# 05_Ethernet.net
KiCad netlist of a schematic drawn in Altium Designer
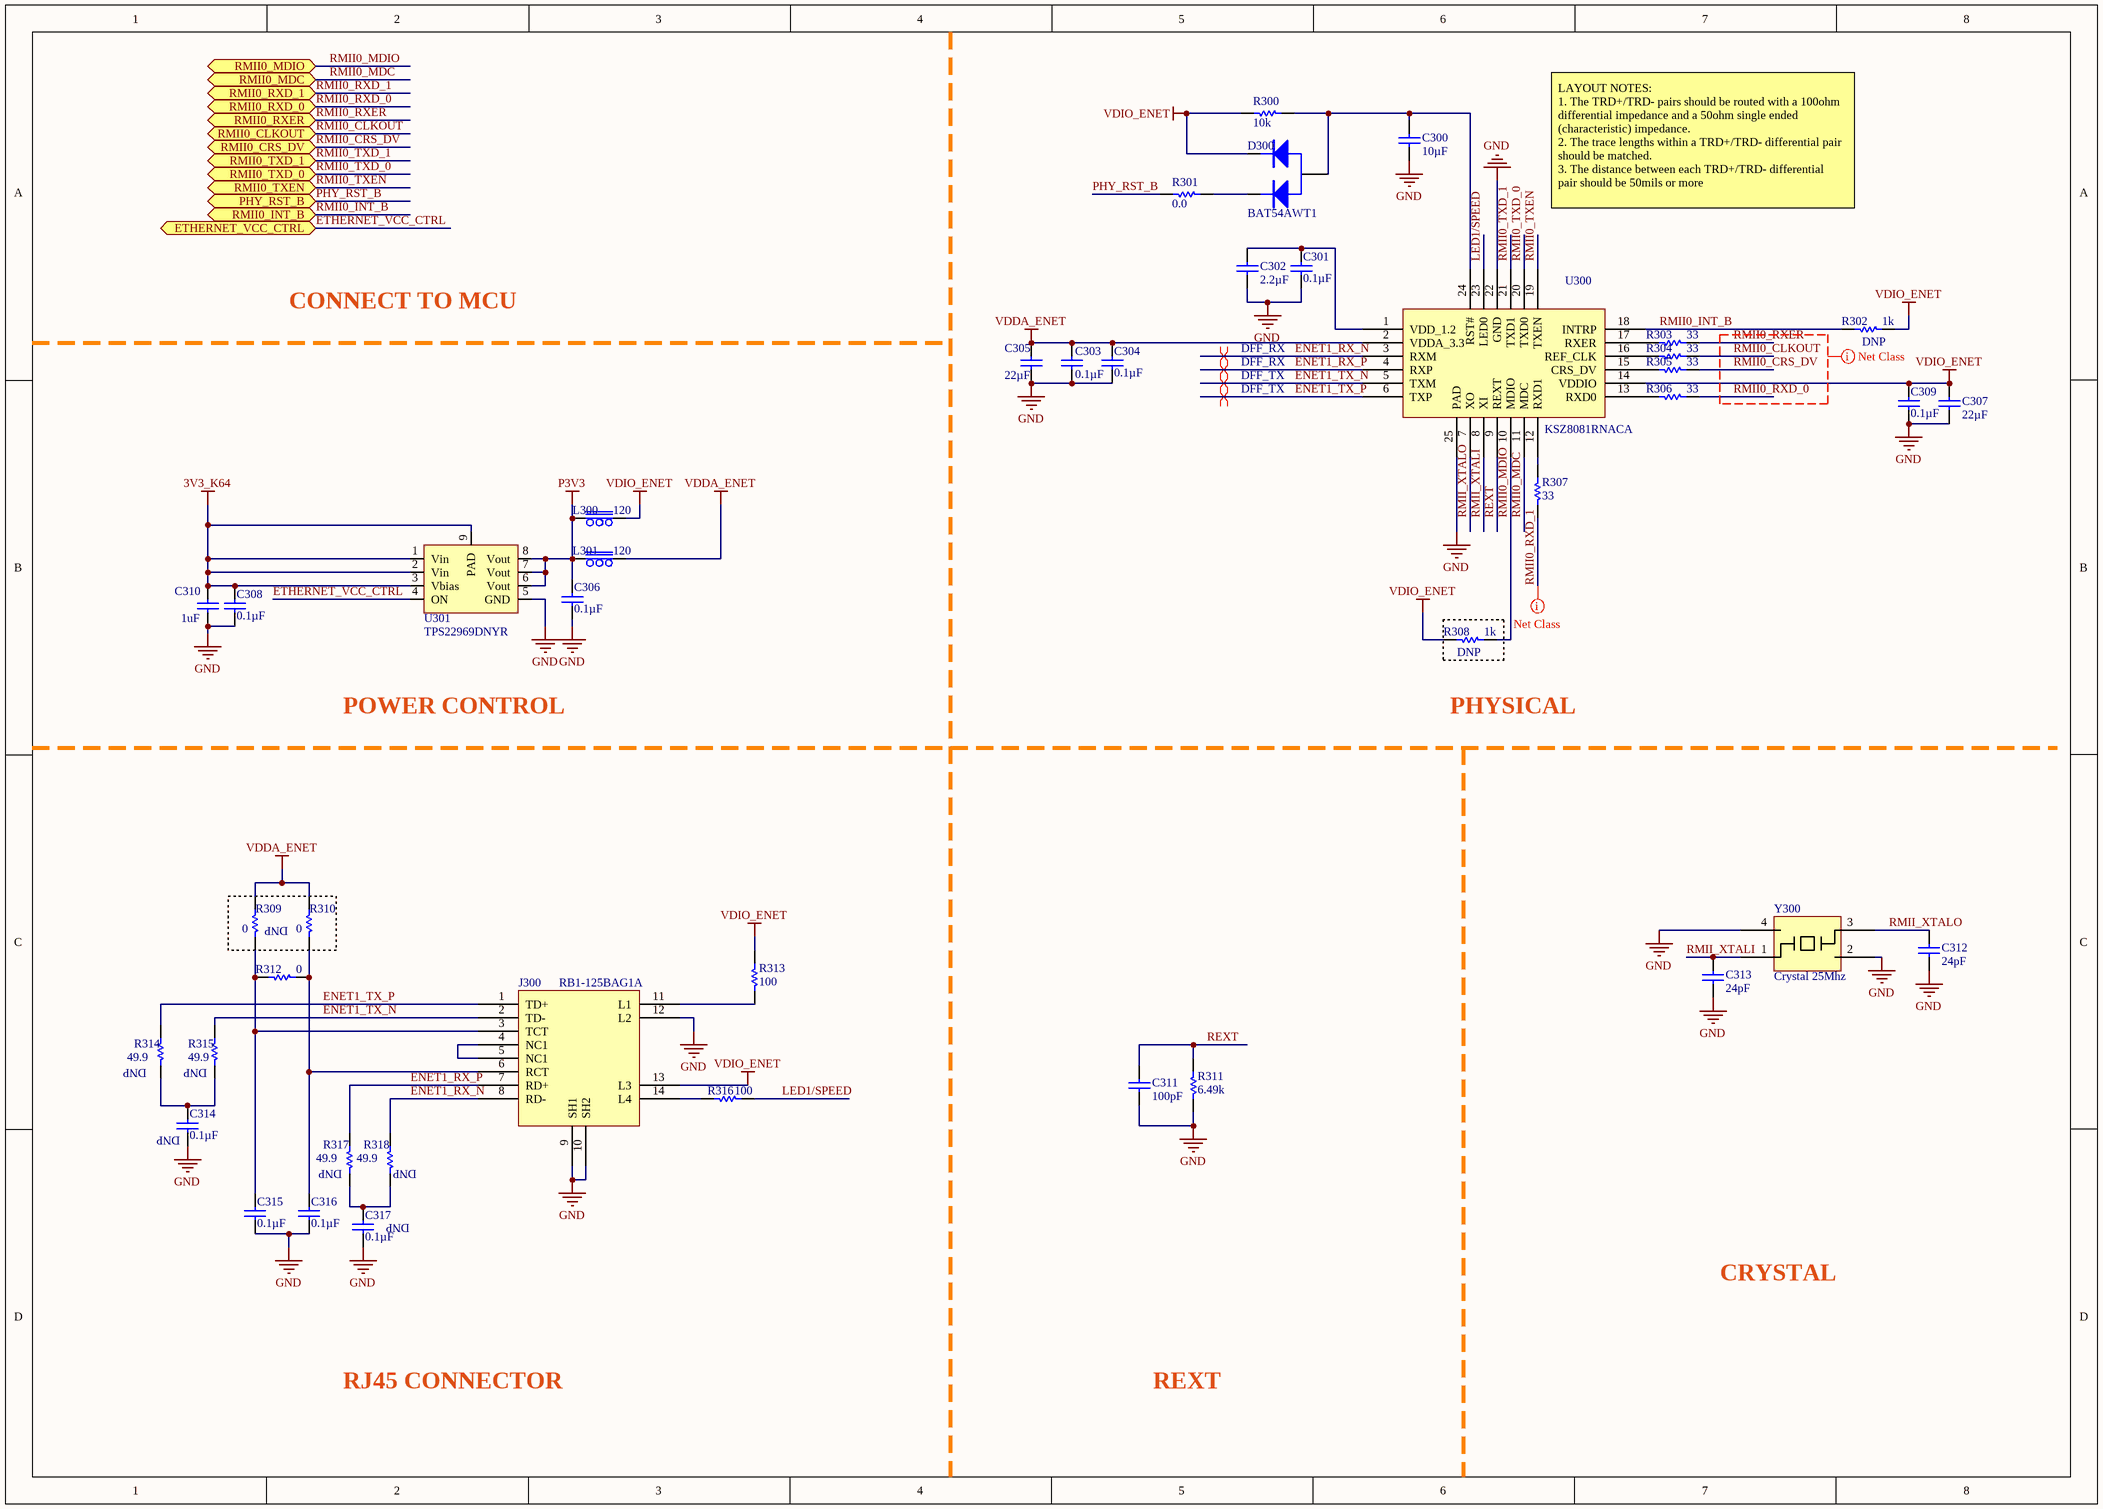
[diagram p0: [05] Ethernet.SchDoc]

(export (version "E")
  (design (tool "Eeschema 10.0.6"))
  (components
    (comp (ref "C300")
      (value "10µF")
      (footprint "0603C")
      (description "CAP CER 10UF 16V X6S 0603")
      (fields
        (field (name "MANUFACTURER") "Taiyo Yuden")
        (field (name "MANUFACTURER PART NUMBER") "EMK107BC6106MA-T")
      )
      (libsource (lib "BinhLib") (part "cap SMD"))
    )
    (comp (ref "C301")
      (value "0.1µF")
      (footprint "0402C")
      (description "CAP CER 0.1UF 10V X7R 0402")
      (fields
        (field (name "MANUFACTURER") "Taiyo Yuden")
        (field (name "MANUFACTURER PART NUMBER") "LMK105B7104KVHF")
      )
      (libsource (lib "BinhLib") (part "CAP0.1u0402"))
    )
    (comp (ref "C302")
      (value "2.2µF")
      (footprint "0402C")
      (description "CAP CER 2.2UF 16V X5R 0402")
      (fields
        (field (name "MANUFACTURER") "Taiyo Yuden")
        (field (name "MANUFACTURER PART NUMBER") "EMK105ABJ225MV-F")
      )
      (libsource (lib "BinhLib") (part "cap2.2u0402"))
    )
    (comp (ref "C303")
      (value "0.1µF")
      (footprint "0402C")
      (description "CAP CER 0.1UF 10V X7R 0402")
      (fields
        (field (name "MANUFACTURER") "Taiyo Yuden")
        (field (name "MANUFACTURER PART NUMBER") "LMK105B7104KVHF")
      )
      (libsource (lib "BinhLib") (part "CAP0.1u0402"))
    )
    (comp (ref "C304")
      (value "0.1µF")
      (footprint "0402C")
      (description "CAP CER 0.1UF 10V X7R 0402")
      (fields
        (field (name "MANUFACTURER") "Taiyo Yuden")
        (field (name "MANUFACTURER PART NUMBER") "LMK105B7104KVHF")
      )
      (libsource (lib "BinhLib") (part "CAP0.1u0402"))
    )
    (comp (ref "C305")
      (value "22µF")
      (footprint "0603C")
      (description "CAP CER 22UF 10V X5R 0603")
      (fields
        (field (name "MANUFACTURER") "Taiyo Yuden")
        (field (name "MANUFACTURER PART NUMBER") "LMK107BBJ226MA-T")
      )
      (libsource (lib "BinhLib") (part "cap SMD"))
    )
    (comp (ref "C306")
      (value "0.1µF")
      (footprint "0402C")
      (description "CAP CER 0.1UF 10V X7R 0402")
      (fields
        (field (name "MANUFACTURER") "Taiyo Yuden")
        (field (name "MANUFACTURER PART NUMBER") "LMK105B7104KVHF")
      )
      (libsource (lib "BinhLib") (part "CAP0.1u0402"))
    )
    (comp (ref "C307")
      (value "22µF")
      (footprint "0603C")
      (description "CAP CER 22UF 10V X5R 0603")
      (fields
        (field (name "MANUFACTURER") "Taiyo Yuden")
        (field (name "MANUFACTURER PART NUMBER") "LMK107BBJ226MA-T")
      )
      (libsource (lib "BinhLib") (part "cap SMD"))
    )
    (comp (ref "C308")
      (value "0.1µF")
      (footprint "0402C")
      (description "CAP CER 0.1UF 10V X7R 0402")
      (fields
        (field (name "MANUFACTURER") "Taiyo Yuden")
        (field (name "MANUFACTURER PART NUMBER") "LMK105B7104KVHF")
      )
      (libsource (lib "BinhLib") (part "CAP0.1u0402"))
    )
    (comp (ref "C309")
      (value "0.1µF")
      (footprint "0402C")
      (description "CAP CER 0.1UF 10V X7R 0402")
      (fields
        (field (name "MANUFACTURER") "Taiyo Yuden")
        (field (name "MANUFACTURER PART NUMBER") "LMK105B7104KVHF")
      )
      (libsource (lib "BinhLib") (part "CAP0.1u0402"))
    )
    (comp (ref "C310")
      (value "1uF")
      (footprint "0402C")
      (description "CAP CER 1UF 10V X6S 0402")
      (fields
        (field (name "MANUFACTURER") "Taiyo Yuden")
        (field (name "MANUFACTURER PART NUMBER") "LMK105C6105KV-F")
      )
      (libsource (lib "BinhLib") (part "cap SMD"))
    )
    (comp (ref "C311")
      (value "100pF")
      (footprint "0603C")
      (description "CAP CER 100PF 250V NP0 0603")
      (fields
        (field (name "MANUFACTURER") "Taiyo Yuden")
        (field (name "MANUFACTURER PART NUMBER") "QVS107CG101JCHT")
      )
      (libsource (lib "BinhLib") (part "cap SMD"))
    )
    (comp (ref "C312")
      (value "24pF")
      (footprint "0402C")
      (description "CAP CER 24PF 50V NP0 0402")
      (fields
        (field (name "MANUFACTURER") "Taiyo Yuden")
        (field (name "MANUFACTURER PART NUMBER") "UMK105CG240JV-F")
      )
      (libsource (lib "BinhLib") (part "cap SMD"))
    )
    (comp (ref "C313")
      (value "24pF")
      (footprint "0402C")
      (description "CAP CER 24PF 50V NP0 0402")
      (fields
        (field (name "MANUFACTURER") "Taiyo Yuden")
        (field (name "MANUFACTURER PART NUMBER") "UMK105CG240JV-F")
      )
      (libsource (lib "BinhLib") (part "cap SMD"))
    )
    (comp (ref "C314")
      (value "0.1µF")
      (footprint "0402C")
      (description "CAP CER 0.1UF 10V X7R 0402")
      (fields
        (field (name "MANUFACTURER") "Taiyo Yuden")
        (field (name "MANUFACTURER PART NUMBER") "LMK105B7104KVHF")
      )
      (libsource (lib "BinhLib") (part "CAP0.1u0402"))
    )
    (comp (ref "C315")
      (value "0.1µF")
      (footprint "0402C")
      (description "CAP CER 0.1UF 10V X7R 0402")
      (fields
        (field (name "MANUFACTURER") "Taiyo Yuden")
        (field (name "MANUFACTURER PART NUMBER") "LMK105B7104KVHF")
      )
      (libsource (lib "BinhLib") (part "CAP0.1u0402"))
    )
    (comp (ref "C316")
      (value "0.1µF")
      (footprint "0402C")
      (description "CAP CER 0.1UF 10V X7R 0402")
      (fields
        (field (name "MANUFACTURER") "Taiyo Yuden")
        (field (name "MANUFACTURER PART NUMBER") "LMK105B7104KVHF")
      )
      (libsource (lib "BinhLib") (part "CAP0.1u0402"))
    )
    (comp (ref "C317")
      (value "0.1µF")
      (footprint "0402C")
      (description "CAP CER 0.1UF 10V X7R 0402")
      (fields
        (field (name "MANUFACTURER") "Taiyo Yuden")
        (field (name "MANUFACTURER PART NUMBER") "LMK105B7104KVHF")
      )
      (libsource (lib "BinhLib") (part "CAP0.1u0402"))
    )
    (comp (ref "D300")
      (value "BAT54AWT1")
      (footprint "SOT323")
      (description "DIODE ARRAY SCHOTTKY 30V SOT323")
      (fields
        (field (name "MANUFACTURER") "ON Semiconductor")
        (field (name "MANUFACTURER PART NUMBER") "BAT54AWT1G")
      )
      (libsource (lib "BinhLib") (part "diodes barrier"))
    )
    (comp (ref "J300")
      (value "RB1-125BAG1A")
      (footprint "RJ45 Tranfomer")
      (description "CONN MAGJACK 1PORT 100 BASE-T")
      (fields (field (name "MANUFACTURER") "WIZnet"))
      (libsource (lib "BinhLib") (part "RJ45"))
    )
    (comp (ref "L300")
      (value "120")
      (footprint "0805F")
      (fields
        (field (name "MANUFACTURER") "MURATA")
        (field (name "MANUFACTURER PART NUMBER") "BLM18PG121SN1D")
      )
      (libsource (lib "BinhLib") (part "Ferrite Bead"))
    )
    (comp (ref "L301")
      (value "120")
      (footprint "0805F")
      (fields
        (field (name "MANUFACTURER") "MURATA")
        (field (name "MANUFACTURER PART NUMBER") "BLM18PG121SN1D")
      )
      (libsource (lib "BinhLib") (part "Ferrite Bead"))
    )
    (comp (ref "R300")
      (value "10k")
      (footprint "0603R")
      (description "RES SMD 10K OHM 1% 1/10W 0603")
      (fields
        (field (name "MANUFACTURER") "Panasonic Electronic Components")
        (field (name "MANUFACTURER PART NUMBER") "ERJ-3EKF1002V")
      )
      (libsource (lib "BinhLib") (part "RES10k0603"))
    )
    (comp (ref "R301")
      (value "0.0")
      (footprint "0603R")
      (description "RES SMD 0.0OHM JUMPER 1/10W 0603")
      (fields
        (field (name "MANUFACTURER") "Panasonic Electronic Components")
        (field (name "MANUFACTURER PART NUMBER") "ERJ-3GEY0R00V")
      )
      (libsource (lib "BinhLib") (part "RES00603"))
    )
    (comp (ref "R302")
      (value "1k")
      (footprint "0402R")
      (description "RES SMD 1K OHM 1% 1/10W 0402")
      (fields
        (field (name "MANUFACTURER") "Panasonic Electronic Components")
        (field (name "MANUFACTURER PART NUMBER") "ERJ-2RKF1001X")
      )
      (libsource (lib "BinhLib") (part "RES1k0402"))
    )
    (comp (ref "R303")
      (value "33")
      (footprint "0402R")
      (description "RES SMD 33 OHM 1% 1/10W 0402")
      (fields
        (field (name "MANUFACTURER") "Panasonic Electronic Components")
        (field (name "MANUFACTURER PART NUMBER") "ERJ-2RKF33R0X")
      )
      (libsource (lib "BinhLib") (part "RES330402"))
    )
    (comp (ref "R304")
      (value "33")
      (footprint "0402R")
      (description "RES SMD 33 OHM 1% 1/10W 0402")
      (fields
        (field (name "MANUFACTURER") "Panasonic Electronic Components")
        (field (name "MANUFACTURER PART NUMBER") "ERJ-2RKF33R0X")
      )
      (libsource (lib "BinhLib") (part "RES330402"))
    )
    (comp (ref "R305")
      (value "33")
      (footprint "0402R")
      (description "RES SMD 33 OHM 1% 1/10W 0402")
      (fields
        (field (name "MANUFACTURER") "Panasonic Electronic Components")
        (field (name "MANUFACTURER PART NUMBER") "ERJ-2RKF33R0X")
      )
      (libsource (lib "BinhLib") (part "RES330402"))
    )
    (comp (ref "R306")
      (value "33")
      (footprint "0402R")
      (description "RES SMD 33 OHM 1% 1/10W 0402")
      (fields
        (field (name "MANUFACTURER") "Panasonic Electronic Components")
        (field (name "MANUFACTURER PART NUMBER") "ERJ-2RKF33R0X")
      )
      (libsource (lib "BinhLib") (part "RES330402"))
    )
    (comp (ref "R307")
      (value "33")
      (footprint "0402R")
      (description "RES SMD 33 OHM 1% 1/10W 0402")
      (fields
        (field (name "MANUFACTURER") "Panasonic Electronic Components")
        (field (name "MANUFACTURER PART NUMBER") "ERJ-2RKF33R0X")
      )
      (libsource (lib "BinhLib") (part "RES330402"))
    )
    (comp (ref "R308")
      (value "1k")
      (footprint "0402R")
      (description "RES SMD 1K OHM 1% 1/10W 0402")
      (fields
        (field (name "MANUFACTURER") "Panasonic Electronic Components")
        (field (name "MANUFACTURER PART NUMBER") "ERJ-2RKF1001X")
      )
      (libsource (lib "BinhLib") (part "RES1k0402"))
    )
    (comp (ref "R309")
      (value "0")
      (footprint "0402R")
      (description "RES SMD 0.0OHM JUMPER 1/10W 0402")
      (fields
        (field (name "MANUFACTURER") "Panasonic Electronic Components")
        (field (name "MANUFACTURER PART NUMBER") "ERJ-2GE0R00X")
      )
      (libsource (lib "BinhLib") (part "RES00603"))
    )
    (comp (ref "R310")
      (value "0")
      (footprint "0402R")
      (description "RES SMD 0.0OHM JUMPER 1/10W 0402")
      (fields
        (field (name "MANUFACTURER") "Panasonic Electronic Components")
        (field (name "MANUFACTURER PART NUMBER") "ERJ-2GE0R00X")
      )
      (libsource (lib "BinhLib") (part "RES00603"))
    )
    (comp (ref "R311")
      (value "6.49k")
      (footprint "0603R")
      (description "RES SMD 6.49KOHM 0.1% 1/10W 0603")
      (fields
        (field (name "MANUFACTURER") "Panasonic Electronic Components")
        (field (name "MANUFACTURER PART NUMBER") "ERA-3AEB6491V")
      )
      (libsource (lib "BinhLib") (part "RES1000603"))
    )
    (comp (ref "R312")
      (value "0")
      (footprint "0402R")
      (description "RES SMD 0.0OHM JUMPER 1/10W 0402")
      (fields
        (field (name "MANUFACTURER") "Panasonic Electronic Components")
        (field (name "MANUFACTURER PART NUMBER") "ERJ-2GE0R00X")
      )
      (libsource (lib "BinhLib") (part "RES00603"))
    )
    (comp (ref "R313")
      (value "100")
      (footprint "0603R")
      (description "RES SMD 100 OHM 1% 1/10W 0603")
      (fields
        (field (name "MANUFACTURER") "Panasonic Electronic Components")
        (field (name "MANUFACTURER PART NUMBER") "ERJ-3EKF1000V")
      )
      (libsource (lib "BinhLib") (part "RES1000603"))
    )
    (comp (ref "R314")
      (value "49.9")
      (footprint "0603R")
      (description "RES SMD 49.9 OHM 1% 1/10W 0603")
      (fields
        (field (name "MANUFACTURER") "Panasonic Electronic Components")
        (field (name "MANUFACTURER PART NUMBER") "ERJ-3EKF49R9V")
      )
      (libsource (lib "BinhLib") (part "Resistor"))
    )
    (comp (ref "R315")
      (value "49.9")
      (footprint "0603R")
      (description "RES SMD 49.9 OHM 1% 1/10W 0603")
      (fields
        (field (name "MANUFACTURER") "Panasonic Electronic Components")
        (field (name "MANUFACTURER PART NUMBER") "ERJ-3EKF49R9V")
      )
      (libsource (lib "BinhLib") (part "Resistor"))
    )
    (comp (ref "R316")
      (value "100")
      (footprint "0603R")
      (description "RES SMD 100 OHM 1% 1/10W 0603")
      (fields
        (field (name "MANUFACTURER") "Panasonic Electronic Components")
        (field (name "MANUFACTURER PART NUMBER") "ERJ-3EKF1000V")
      )
      (libsource (lib "BinhLib") (part "RES1000603"))
    )
    (comp (ref "R317")
      (value "49.9")
      (footprint "0603R")
      (description "RES SMD 49.9 OHM 1% 1/10W 0603")
      (fields
        (field (name "MANUFACTURER") "Panasonic Electronic Components")
        (field (name "MANUFACTURER PART NUMBER") "ERJ-3EKF49R9V")
      )
      (libsource (lib "BinhLib") (part "Resistor"))
    )
    (comp (ref "R318")
      (value "49.9")
      (footprint "0603R")
      (description "RES SMD 49.9 OHM 1% 1/10W 0603")
      (fields
        (field (name "MANUFACTURER") "Panasonic Electronic Components")
        (field (name "MANUFACTURER PART NUMBER") "ERJ-3EKF49R9V")
      )
      (libsource (lib "BinhLib") (part "Resistor"))
    )
    (comp (ref "U300")
      (value "KSZ8081RNACA")
      (footprint "QFN24x")
      (description "IC TXRX ETHERNET 24QFN")
      (fields
        (field (name "MANUFACTURER") "Microchip Technology")
        (field (name "MANUFACTURER PART NUMBER") "KSZ8081RNACA-TR")
      )
      (libsource (lib "BinhLib") (part "KSZ8081RNACA"))
    )
    (comp (ref "U301")
      (value "TPS22969DNYR")
      (footprint "WSON8")
      (description "IC LOAD SWITCH 6A 8WSON")
      (fields (field (name "MANUFACTURER") "Texas Instruments"))
      (libsource (lib "BinhLib") (part "TPS22969"))
    )
    (comp (ref "Y300")
      (value "Crystal 25Mhz")
      (footprint "3225 cry")
      (description "CRYSTAL 25.0000MHZ 18PF SMD")
      (fields
        (field (name "MANUFACTURER") "CTS-Frequency Controls")
        (field (name "MANUFACTURER PART NUMBER") "403I35D25M00000")
      )
      (libsource (lib "BinhLib") (part "Crystal 25Mhz"))
    )
  )
  (nets
    (net (code "1") (name "/ENET1_RX_N") (class "Default")
      (node (ref "J300") (pin "8") (pinfunction "RD-_8") (pintype "passive"))
      (node (ref "R318") (pin "2") (pinfunction "2_2") (pintype "passive"))
      (node (ref "U300") (pin "3") (pinfunction "RXM_3") (pintype "passive"))
    )
    (net (code "2") (name "/ENET1_RX_P") (class "Default")
      (node (ref "J300") (pin "7") (pinfunction "RD+_7") (pintype "passive"))
      (node (ref "R317") (pin "2") (pinfunction "2_2") (pintype "passive"))
      (node (ref "U300") (pin "4") (pinfunction "RXP_4") (pintype "passive"))
    )
    (net (code "3") (name "/ENET1_TX_N") (class "Default")
      (node (ref "J300") (pin "2") (pinfunction "TD-_2") (pintype "passive"))
      (node (ref "R315") (pin "2") (pinfunction "2_2") (pintype "passive"))
      (node (ref "U300") (pin "5") (pinfunction "TXM_5") (pintype "passive"))
    )
    (net (code "4") (name "/ENET1_TX_P") (class "Default")
      (node (ref "J300") (pin "1") (pinfunction "TD+_1") (pintype "passive"))
      (node (ref "R314") (pin "2") (pinfunction "2_2") (pintype "passive"))
      (node (ref "U300") (pin "6") (pinfunction "TXP_6") (pintype "passive"))
    )
    (net (code "5") (name "/ETHERNET_VCC_CTRL") (class "Default")
      (node (ref "U301") (pin "4") (pinfunction "ON_4") (pintype "passive"))
    )
    (net (code "6") (name "/LED1{slash}SPEED") (class "Default")
      (node (ref "R316") (pin "2") (pinfunction "2_2") (pintype "passive"))
      (node (ref "U300") (pin "23") (pinfunction "LED0_23") (pintype "passive"))
    )
    (net (code "7") (name "/PHY_RST_B") (class "Default")
      (node (ref "R301") (pin "1") (pinfunction "1_1") (pintype "passive"))
    )
    (net (code "8") (name "/REXT") (class "Default")
      (node (ref "C311") (pin "2") (pintype "passive"))
      (node (ref "R311") (pin "2") (pinfunction "2_2") (pintype "passive"))
      (node (ref "U300") (pin "9") (pinfunction "REXT_9") (pintype "passive"))
    )
    (net (code "9") (name "/RMII0_CLKOUT") (class "Default")
      (node (ref "R304") (pin "2") (pinfunction "2_2") (pintype "passive"))
    )
    (net (code "10") (name "/RMII0_CRS_DV") (class "Default")
      (node (ref "R305") (pin "2") (pinfunction "2_2") (pintype "passive"))
    )
    (net (code "11") (name "/RMII0_INT_B") (class "Default")
      (node (ref "R302") (pin "1") (pinfunction "1_1") (pintype "passive"))
      (node (ref "U300") (pin "18") (pinfunction "INTRP_18") (pintype "passive"))
    )
    (net (code "12") (name "/RMII0_MDC") (class "Default")
      (node (ref "U300") (pin "11") (pinfunction "MDC_11") (pintype "passive"))
    )
    (net (code "13") (name "/RMII0_MDIO") (class "Default")
      (node (ref "R308") (pin "2") (pinfunction "2_2") (pintype "passive"))
      (node (ref "U300") (pin "10") (pinfunction "MDIO_10") (pintype "passive"))
    )
    (net (code "14") (name "/RMII0_RXD_0") (class "Default")
      (node (ref "R306") (pin "2") (pinfunction "2_2") (pintype "passive"))
    )
    (net (code "15") (name "/RMII0_RXD_1") (class "Default")
      (node (ref "R307") (pin "1") (pinfunction "1_1") (pintype "passive"))
    )
    (net (code "16") (name "/RMII0_RXER") (class "Default")
      (node (ref "R303") (pin "2") (pinfunction "2_2") (pintype "passive"))
    )
    (net (code "17") (name "/RMII0_TXD_0") (class "Default")
      (node (ref "U300") (pin "20") (pinfunction "TXD0_20") (pintype "passive"))
    )
    (net (code "18") (name "/RMII0_TXD_1") (class "Default")
      (node (ref "U300") (pin "21") (pinfunction "TXD1_21") (pintype "passive"))
    )
    (net (code "19") (name "/RMII0_TXEN") (class "Default")
      (node (ref "U300") (pin "19") (pinfunction "TXEN_19") (pintype "passive"))
    )
    (net (code "20") (name "/RMII_XTALI") (class "Default")
      (node (ref "C313") (pin "2") (pintype "passive"))
      (node (ref "U300") (pin "8") (pinfunction "XI_8") (pintype "passive"))
      (node (ref "Y300") (pin "1") (pintype "passive"))
    )
    (net (code "21") (name "/RMII_XTALO") (class "Default")
      (node (ref "C312") (pin "2") (pintype "passive"))
      (node (ref "U300") (pin "7") (pinfunction "XO_7") (pintype "passive"))
      (node (ref "Y300") (pin "3") (pintype "passive"))
    )
    (net (code "22") (name "3V3_K64") (class "Default")
      (node (ref "C308") (pin "2") (pintype "passive"))
      (node (ref "C310") (pin "2") (pintype "passive"))
      (node (ref "U301") (pin "1") (pinfunction "Vin_1") (pintype "passive"))
      (node (ref "U301") (pin "2") (pinfunction "Vin_2") (pintype "passive"))
      (node (ref "U301") (pin "3") (pinfunction "Vbias_3") (pintype "passive"))
      (node (ref "U301") (pin "9") (pinfunction "PAD_9") (pintype "passive"))
    )
    (net (code "23") (name "GND") (class "Default")
      (node (ref "C300") (pin "1") (pintype "passive"))
      (node (ref "C301") (pin "1") (pintype "passive"))
      (node (ref "C302") (pin "1") (pintype "passive"))
      (node (ref "C303") (pin "1") (pintype "passive"))
      (node (ref "C304") (pin "1") (pintype "passive"))
      (node (ref "C305") (pin "1") (pintype "passive"))
      (node (ref "C306") (pin "1") (pintype "passive"))
      (node (ref "C307") (pin "1") (pintype "passive"))
      (node (ref "C308") (pin "1") (pintype "passive"))
      (node (ref "C309") (pin "1") (pintype "passive"))
      (node (ref "C310") (pin "1") (pintype "passive"))
      (node (ref "C311") (pin "1") (pintype "passive"))
      (node (ref "C312") (pin "1") (pintype "passive"))
      (node (ref "C313") (pin "1") (pintype "passive"))
      (node (ref "C314") (pin "1") (pintype "passive"))
      (node (ref "C315") (pin "1") (pintype "passive"))
      (node (ref "C316") (pin "1") (pintype "passive"))
      (node (ref "C317") (pin "1") (pintype "passive"))
      (node (ref "J300") (pin "10") (pinfunction "SH2_10") (pintype "passive"))
      (node (ref "J300") (pin "12") (pinfunction "L2_12") (pintype "passive"))
      (node (ref "J300") (pin "9") (pinfunction "SH1_9") (pintype "passive"))
      (node (ref "R311") (pin "1") (pinfunction "1_1") (pintype "passive"))
      (node (ref "U300") (pin "22") (pinfunction "GND_22") (pintype "passive"))
      (node (ref "U300") (pin "25") (pinfunction "PAD_25") (pintype "passive"))
      (node (ref "U301") (pin "5") (pinfunction "GND_5") (pintype "passive"))
      (node (ref "Y300") (pin "2") (pintype "passive"))
      (node (ref "Y300") (pin "4") (pintype "passive"))
    )
    (net (code "24") (name "Net-(C314-Pad2)") (class "Default")
      (node (ref "C314") (pin "2") (pintype "passive"))
      (node (ref "R314") (pin "1") (pinfunction "1_1") (pintype "passive"))
      (node (ref "R315") (pin "1") (pinfunction "1_1") (pintype "passive"))
    )
    (net (code "25") (name "Net-(C317-Pad2)") (class "Default")
      (node (ref "C317") (pin "2") (pintype "passive"))
      (node (ref "R317") (pin "1") (pinfunction "1_1") (pintype "passive"))
      (node (ref "R318") (pin "1") (pinfunction "1_1") (pintype "passive"))
    )
    (net (code "26") (name "Net-(D300-Pad2)") (class "Default")
      (node (ref "D300") (pin "2") (pinfunction "2_2") (pintype "passive"))
      (node (ref "R301") (pin "2") (pinfunction "2_2") (pintype "passive"))
    )
    (net (code "27") (name "Net-(J300-L1)") (class "Default")
      (node (ref "J300") (pin "11") (pinfunction "L1_11") (pintype "passive"))
      (node (ref "R313") (pin "1") (pinfunction "1_1") (pintype "passive"))
    )
    (net (code "28") (name "Net-(J300-L4)") (class "Default")
      (node (ref "J300") (pin "14") (pinfunction "L4_14") (pintype "passive"))
      (node (ref "R316") (pin "1") (pinfunction "1_1") (pintype "passive"))
    )
    (net (code "29") (name "Net-(J300-NC1-Pad4)") (class "Default")
      (node (ref "J300") (pin "4") (pinfunction "NC1_4") (pintype "passive"))
      (node (ref "J300") (pin "5") (pinfunction "NC1_5") (pintype "passive"))
    )
    (net (code "30") (name "Net-(J300-RCT)") (class "Default")
      (node (ref "C316") (pin "2") (pintype "passive"))
      (node (ref "J300") (pin "6") (pinfunction "RCT_6") (pintype "passive"))
      (node (ref "R310") (pin "1") (pinfunction "1_1") (pintype "passive"))
      (node (ref "R312") (pin "1") (pinfunction "1_1") (pintype "passive"))
    )
    (net (code "31") (name "Net-(J300-TCT)") (class "Default")
      (node (ref "C315") (pin "2") (pintype "passive"))
      (node (ref "J300") (pin "3") (pinfunction "TCT_3") (pintype "passive"))
      (node (ref "R309") (pin "1") (pinfunction "1_1") (pintype "passive"))
      (node (ref "R312") (pin "2") (pinfunction "2_2") (pintype "passive"))
    )
    (net (code "32") (name "Net-(U300-CRS_DV)") (class "Default")
      (node (ref "R305") (pin "1") (pinfunction "1_1") (pintype "passive"))
      (node (ref "U300") (pin "15") (pinfunction "CRS_DV_15") (pintype "passive"))
    )
    (net (code "33") (name "Net-(U300-REF_CLK)") (class "Default")
      (node (ref "R304") (pin "1") (pinfunction "1_1") (pintype "passive"))
      (node (ref "U300") (pin "16") (pinfunction "REF_CLK_16") (pintype "passive"))
    )
    (net (code "34") (name "Net-(U300-RST#)") (class "Default")
      (node (ref "C300") (pin "2") (pintype "passive"))
      (node (ref "D300") (pin "3") (pinfunction "3_3") (pintype "passive"))
      (node (ref "R300") (pin "2") (pinfunction "2_2") (pintype "passive"))
      (node (ref "U300") (pin "24") (pinfunction "RST#_24") (pintype "passive"))
    )
    (net (code "35") (name "Net-(U300-RXD0)") (class "Default")
      (node (ref "R306") (pin "1") (pinfunction "1_1") (pintype "passive"))
      (node (ref "U300") (pin "13") (pinfunction "RXD0_13") (pintype "passive"))
    )
    (net (code "36") (name "Net-(U300-RXD1)") (class "Default")
      (node (ref "R307") (pin "2") (pinfunction "2_2") (pintype "passive"))
      (node (ref "U300") (pin "12") (pinfunction "RXD1_12") (pintype "passive"))
    )
    (net (code "37") (name "Net-(U300-RXER)") (class "Default")
      (node (ref "R303") (pin "1") (pinfunction "1_1") (pintype "passive"))
      (node (ref "U300") (pin "17") (pinfunction "RXER_17") (pintype "passive"))
    )
    (net (code "38") (name "Net-(U300-VDD_1.2)") (class "Default")
      (node (ref "C301") (pin "2") (pintype "passive"))
      (node (ref "C302") (pin "2") (pintype "passive"))
      (node (ref "U300") (pin "1") (pinfunction "VDD_1.2_1") (pintype "passive"))
    )
    (net (code "39") (name "P3V3") (class "Default")
      (node (ref "C306") (pin "2") (pintype "passive"))
      (node (ref "L300") (pin "1") (pintype "passive"))
      (node (ref "L301") (pin "1") (pintype "passive"))
      (node (ref "U301") (pin "6") (pinfunction "Vout_6") (pintype "passive"))
      (node (ref "U301") (pin "7") (pinfunction "Vout_7") (pintype "passive"))
      (node (ref "U301") (pin "8") (pinfunction "Vout_8") (pintype "passive"))
    )
    (net (code "40") (name "VDDA_ENET") (class "Default")
      (node (ref "C303") (pin "2") (pintype "passive"))
      (node (ref "C304") (pin "2") (pintype "passive"))
      (node (ref "C305") (pin "2") (pintype "passive"))
      (node (ref "L301") (pin "2") (pintype "passive"))
      (node (ref "R309") (pin "2") (pinfunction "2_2") (pintype "passive"))
      (node (ref "R310") (pin "2") (pinfunction "2_2") (pintype "passive"))
      (node (ref "U300") (pin "2") (pinfunction "VDDA_3.3_2") (pintype "passive"))
    )
    (net (code "41") (name "VDIO_ENET") (class "Default")
      (node (ref "C307") (pin "2") (pintype "passive"))
      (node (ref "C309") (pin "2") (pintype "passive"))
      (node (ref "D300") (pin "1") (pinfunction "1_1") (pintype "passive"))
      (node (ref "J300") (pin "13") (pinfunction "L3_13") (pintype "passive"))
      (node (ref "L300") (pin "2") (pintype "passive"))
      (node (ref "R300") (pin "1") (pinfunction "1_1") (pintype "passive"))
      (node (ref "R302") (pin "2") (pinfunction "2_2") (pintype "passive"))
      (node (ref "R308") (pin "1") (pinfunction "1_1") (pintype "passive"))
      (node (ref "R313") (pin "2") (pinfunction "2_2") (pintype "passive"))
      (node (ref "U300") (pin "14") (pinfunction "VDDIO_14") (pintype "passive"))
    )
  )
)
